# esp8266Duino.net
KiCad netlist of a schematic drawn in EAGLE
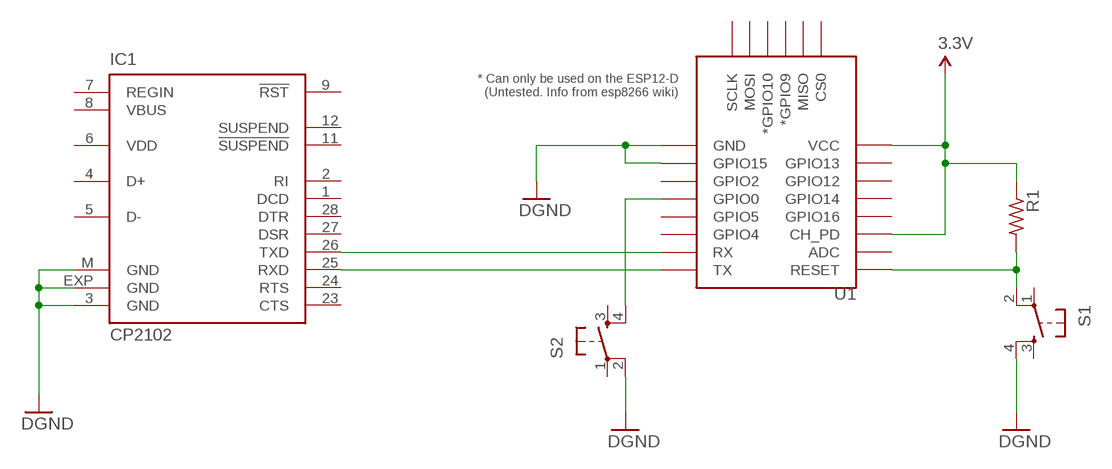
[diagram p0: schematic, sheet 1]

(export (version "E")
  (design (tool "Eeschema 10.0.6"))
  (components
    (comp (ref "IC1")
      (value "CP2102")
      (footprint "eagle-import:MLP28")
      (fields (field (name "MF") "FARNELL") (field (name "MPN") "CP2102-GM"))
      (libsource (lib "eagle-import") (part "CP2102"))
    )
    (comp (ref "R1")
      (value "R-US_0204/2V")
      (footprint "eagle-import:0204V")
      (libsource (lib "eagle-import") (part "R-US_0204/2V"))
    )
    (comp (ref "S1")
      (value "TAC_SWITCHPTH")
      (footprint "eagle-import:TACTILE-PTH")
      (libsource (lib "eagle-import") (part "TAC_SWITCHPTH"))
    )
    (comp (ref "S2")
      (value "TAC_SWITCHPTH")
      (footprint "eagle-import:TACTILE-PTH")
      (libsource (lib "eagle-import") (part "TAC_SWITCHPTH"))
    )
    (comp (ref "U1")
      (value "ESP12ESMD")
      (footprint "eagle-import:ESP12E-SMD")
      (libsource (lib "eagle-import") (part "ESP12ESMD"))
    )
  )
  (nets
    (net (code "1") (name "/VDD") (class "Default")
      (node (ref "IC1") (pin "6") (pinfunction "VDD_6") (pintype "power_in"))
    )
    (net (code "2") (name "3.3V") (class "Default")
      (node (ref "R1") (pin "1") (pinfunction "1_1") (pintype "passive"))
      (node (ref "U1") (pin "CH_PD") (pinfunction "CH_PD_CH_PD") (pintype "bidirectional"))
      (node (ref "U1") (pin "VCC") (pinfunction "VCC_VCC") (pintype "bidirectional"))
    )
    (net (code "3") (name "DGND") (class "Default")
      (node (ref "IC1") (pin "3") (pinfunction "GND_3") (pintype "power_in"))
      (node (ref "IC1") (pin "EXP") (pinfunction "GND_EXP") (pintype "power_in"))
      (node (ref "IC1") (pin "M") (pinfunction "GND_M") (pintype "power_in"))
      (node (ref "S1") (pin "4") (pinfunction "4_4") (pintype "passive"))
      (node (ref "S2") (pin "2") (pinfunction "2_2") (pintype "passive"))
      (node (ref "U1") (pin "GND") (pinfunction "GND_GND") (pintype "bidirectional"))
      (node (ref "U1") (pin "GPIO15") (pinfunction "GPIO15_GPIO15") (pintype "bidirectional"))
    )
    (net (code "4") (name "Net-(IC1-RXD)") (class "Default")
      (node (ref "IC1") (pin "25") (pinfunction "RXD_25") (pintype "input"))
      (node (ref "U1") (pin "TXD0") (pinfunction "TX_TXD0") (pintype "bidirectional"))
    )
    (net (code "5") (name "Net-(IC1-TXD)") (class "Default")
      (node (ref "IC1") (pin "26") (pinfunction "TXD_26") (pintype "output"))
      (node (ref "U1") (pin "RXD0") (pinfunction "RX_RXD0") (pintype "bidirectional"))
    )
    (net (code "6") (name "Net-(R1-Pad2)") (class "Default")
      (node (ref "R1") (pin "2") (pinfunction "2_2") (pintype "passive"))
      (node (ref "S1") (pin "2") (pinfunction "2_2") (pintype "passive"))
      (node (ref "U1") (pin "RESET") (pinfunction "RESET_RESET") (pintype "bidirectional"))
    )
    (net (code "7") (name "Net-(S2-Pad4)") (class "Default")
      (node (ref "S2") (pin "4") (pinfunction "4_4") (pintype "passive"))
      (node (ref "U1") (pin "GPIO0") (pinfunction "GPIO0_GPIO0") (pintype "bidirectional"))
    )
    (net (code "8") (name "unconnected-(IC1-CTS-Pad23)") (class "Default")
      (node (ref "IC1") (pin "23") (pinfunction "CTS_23") (pintype "input"))
    )
    (net (code "9") (name "unconnected-(IC1-D+-Pad4)") (class "Default")
      (node (ref "IC1") (pin "4") (pinfunction "D+_4") (pintype "bidirectional"))
    )
    (net (code "10") (name "unconnected-(IC1-D--Pad5)") (class "Default")
      (node (ref "IC1") (pin "5") (pinfunction "D-_5") (pintype "bidirectional"))
    )
    (net (code "11") (name "unconnected-(IC1-DCD-Pad1)") (class "Default")
      (node (ref "IC1") (pin "1") (pinfunction "DCD_1") (pintype "input"))
    )
    (net (code "12") (name "unconnected-(IC1-DSR-Pad27)") (class "Default")
      (node (ref "IC1") (pin "27") (pinfunction "DSR_27") (pintype "input"))
    )
    (net (code "13") (name "unconnected-(IC1-DTR-Pad28)") (class "Default")
      (node (ref "IC1") (pin "28") (pinfunction "DTR_28") (pintype "output"))
    )
    (net (code "14") (name "unconnected-(IC1-REGIN-Pad7)") (class "Default")
      (node (ref "IC1") (pin "7") (pinfunction "REGIN_7") (pintype "passive"))
    )
    (net (code "15") (name "unconnected-(IC1-RI-Pad2)") (class "Default")
      (node (ref "IC1") (pin "2") (pinfunction "RI_2") (pintype "input"))
    )
    (net (code "16") (name "unconnected-(IC1-RTS-Pad24)") (class "Default")
      (node (ref "IC1") (pin "24") (pinfunction "RTS_24") (pintype "output"))
    )
    (net (code "17") (name "unconnected-(IC1-SUSPEND-Pad12)") (class "Default")
      (node (ref "IC1") (pin "12") (pinfunction "SUSPEND_12") (pintype "output"))
    )
    (net (code "18") (name "unconnected-(IC1-VBUS-Pad8)") (class "Default")
      (node (ref "IC1") (pin "8") (pinfunction "VBUS_8") (pintype "input"))
    )
    (net (code "19") (name "unconnected-(IC1-~{RST}-Pad9)") (class "Default")
      (node (ref "IC1") (pin "9") (pinfunction "~{RST}_9") (pintype "bidirectional"))
    )
    (net (code "20") (name "unconnected-(IC1-~{SUSPEND}-Pad11)") (class "Default")
      (node (ref "IC1") (pin "11") (pinfunction "~{SUSPEND}_11") (pintype "output"))
    )
    (net (code "21") (name "unconnected-(S1-Pad1)") (class "Default")
      (node (ref "S1") (pin "1") (pinfunction "1_1") (pintype "passive"))
    )
    (net (code "22") (name "unconnected-(S1-Pad3)") (class "Default")
      (node (ref "S1") (pin "3") (pinfunction "3_3") (pintype "passive"))
    )
    (net (code "23") (name "unconnected-(S2-Pad1)") (class "Default")
      (node (ref "S2") (pin "1") (pinfunction "1_1") (pintype "passive"))
    )
    (net (code "24") (name "unconnected-(S2-Pad3)") (class "Default")
      (node (ref "S2") (pin "3") (pinfunction "3_3") (pintype "passive"))
    )
    (net (code "25") (name "unconnected-(U1-*GPIO9-PadGPIO9)") (class "Default")
      (node (ref "U1") (pin "GPIO9") (pinfunction "*GPIO9_GPIO9") (pintype "bidirectional"))
    )
    (net (code "26") (name "unconnected-(U1-*GPIO10-PadGPIO10)") (class "Default")
      (node (ref "U1") (pin "GPIO10") (pinfunction "*GPIO10_GPIO10") (pintype "bidirectional"))
    )
    (net (code "27") (name "unconnected-(U1-PadADC)") (class "Default")
      (node (ref "U1") (pin "ADC") (pinfunction "ADC_ADC") (pintype "bidirectional"))
    )
    (net (code "28") (name "unconnected-(U1-PadCS0)") (class "Default")
      (node (ref "U1") (pin "CS0") (pinfunction "CS0_CS0") (pintype "bidirectional"))
    )
    (net (code "29") (name "unconnected-(U1-PadGPIO2)") (class "Default")
      (node (ref "U1") (pin "GPIO2") (pinfunction "GPIO2_GPIO2") (pintype "bidirectional"))
    )
    (net (code "30") (name "unconnected-(U1-PadGPIO4)") (class "Default")
      (node (ref "U1") (pin "GPIO4") (pinfunction "GPIO4_GPIO4") (pintype "bidirectional"))
    )
    (net (code "31") (name "unconnected-(U1-PadGPIO5)") (class "Default")
      (node (ref "U1") (pin "GPIO5") (pinfunction "GPIO5_GPIO5") (pintype "bidirectional"))
    )
    (net (code "32") (name "unconnected-(U1-PadGPIO12)") (class "Default")
      (node (ref "U1") (pin "GPIO12") (pinfunction "GPIO12_GPIO12") (pintype "bidirectional"))
    )
    (net (code "33") (name "unconnected-(U1-PadGPIO13)") (class "Default")
      (node (ref "U1") (pin "GPIO13") (pinfunction "GPIO13_GPIO13") (pintype "bidirectional"))
    )
    (net (code "34") (name "unconnected-(U1-PadGPIO14)") (class "Default")
      (node (ref "U1") (pin "GPIO14") (pinfunction "GPIO14_GPIO14") (pintype "bidirectional"))
    )
    (net (code "35") (name "unconnected-(U1-PadGPIO16)") (class "Default")
      (node (ref "U1") (pin "GPIO16") (pinfunction "GPIO16_GPIO16") (pintype "bidirectional"))
    )
    (net (code "36") (name "unconnected-(U1-PadMISO)") (class "Default")
      (node (ref "U1") (pin "MISO") (pinfunction "MISO_MISO") (pintype "bidirectional"))
    )
    (net (code "37") (name "unconnected-(U1-PadMOSI)") (class "Default")
      (node (ref "U1") (pin "MOSI") (pinfunction "MOSI_MOSI") (pintype "bidirectional"))
    )
    (net (code "38") (name "unconnected-(U1-PadSCLK)") (class "Default")
      (node (ref "U1") (pin "SCLK") (pinfunction "SCLK_SCLK") (pintype "bidirectional"))
    )
  )
)
